# LightBox_Schematic_Updated_11-26.net
KiCad netlist of a schematic drawn in EAGLE
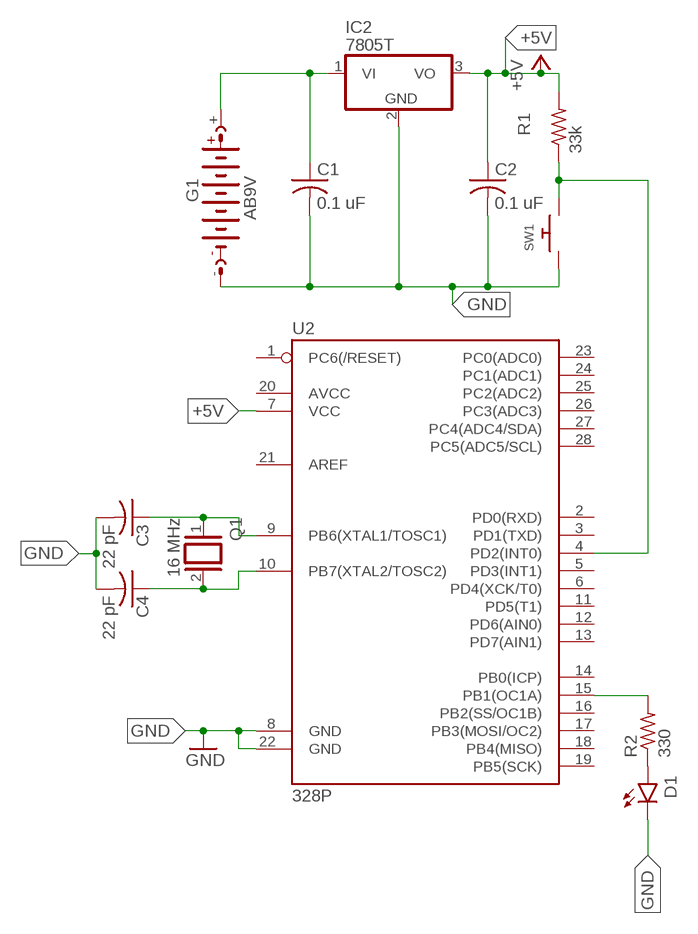
[diagram p0: schematic, sheet 1]

(export (version "E")
  (design (tool "Eeschema 10.0.6"))
  (components
    (comp (ref "C1")
      (value "0.1 uF")
      (footprint "eagle-import:C0805")
      (libsource (lib "eagle-import") (part "C-USC0805"))
    )
    (comp (ref "C2")
      (value "0.1 uF")
      (footprint "eagle-import:C0805")
      (libsource (lib "eagle-import") (part "C-USC0805"))
    )
    (comp (ref "C3")
      (value "22 pF")
      (footprint "eagle-import:C0805")
      (libsource (lib "eagle-import") (part "C-USC0805"))
    )
    (comp (ref "C4")
      (value "22 pF")
      (footprint "eagle-import:C0805")
      (libsource (lib "eagle-import") (part "C-USC0805"))
    )
    (comp (ref "D1")
      (value "LED3MM")
      (footprint "eagle-import:LED_3MM")
      (libsource (lib "eagle-import") (part "LED3MM"))
    )
    (comp (ref "G1")
      (value "AB9V")
      (footprint "eagle-import:AB9V")
      (libsource (lib "eagle-import") (part "AB9V"))
    )
    (comp (ref "IC2")
      (value "7805T")
      (footprint "eagle-import:TO220H")
      (libsource (lib "eagle-import") (part "78T05"))
    )
    (comp (ref "Q1")
      (value "16 MHz")
      (footprint "eagle-import:QS")
      (libsource (lib "eagle-import") (part "XTAL/S"))
    )
    (comp (ref "R1")
      (value "33k")
      (footprint "eagle-import:R0805")
      (libsource (lib "eagle-import") (part "R-US_R0805"))
    )
    (comp (ref "R2")
      (value "330")
      (footprint "eagle-import:R0805")
      (libsource (lib "eagle-import") (part "R-US_R0805"))
    )
    (comp (ref "SW1")
      (value "SWITCH_PUSHBUTTONEVQ-PE")
      (footprint "eagle-import:TACT_PANA-EVQ")
      (libsource (lib "eagle-import") (part "SWITCH_PUSHBUTTONEVQ-PE"))
    )
    (comp (ref "U2")
      (value "328P")
      (footprint "eagle-import:DIP28")
      (libsource (lib "eagle-import") (part "ATMEGA328P_PDIP"))
    )
  )
  (nets
    (net (code "1") (name "+5V") (class "Default")
      (node (ref "C2") (pin "1") (pinfunction "1_1") (pintype "passive"))
      (node (ref "IC2") (pin "3") (pinfunction "VO_3") (pintype "passive"))
      (node (ref "R1") (pin "1") (pinfunction "1_1") (pintype "passive"))
      (node (ref "R1") (pin "2") (pinfunction "2_2") (pintype "passive"))
      (node (ref "SW1") (pin "P$2") (pinfunction "P$2_P$2") (pintype "passive"))
      (node (ref "U2") (pin "4") (pinfunction "PD2(INT0)_4") (pintype "bidirectional"))
      (node (ref "U2") (pin "7") (pinfunction "VCC_7") (pintype "bidirectional"))
    )
    (net (code "2") (name "GND") (class "Default")
      (node (ref "C1") (pin "2") (pinfunction "2_2") (pintype "passive"))
      (node (ref "C2") (pin "2") (pinfunction "2_2") (pintype "passive"))
      (node (ref "C3") (pin "2") (pinfunction "2_2") (pintype "passive"))
      (node (ref "C4") (pin "2") (pinfunction "2_2") (pintype "passive"))
      (node (ref "D1") (pin "K") (pinfunction "C_K") (pintype "passive"))
      (node (ref "G1") (pin "-") (pinfunction "-_-") (pintype "passive"))
      (node (ref "IC2") (pin "2") (pinfunction "GND_2") (pintype "passive"))
      (node (ref "SW1") (pin "P$1") (pinfunction "P$1_P$1") (pintype "passive"))
      (node (ref "U2") (pin "22") (pinfunction "GND_22") (pintype "bidirectional"))
      (node (ref "U2") (pin "8") (pinfunction "GND_8") (pintype "bidirectional"))
    )
    (net (code "3") (name "Net-(D1-PadA)") (class "Default")
      (node (ref "D1") (pin "A") (pinfunction "A_A") (pintype "passive"))
      (node (ref "R2") (pin "1") (pinfunction "1_1") (pintype "passive"))
    )
    (net (code "4") (name "Net-(IC2-VI)") (class "Default")
      (node (ref "C1") (pin "1") (pinfunction "1_1") (pintype "passive"))
      (node (ref "G1") (pin "+") (pinfunction "+_+") (pintype "passive"))
      (node (ref "IC2") (pin "1") (pinfunction "VI_1") (pintype "input"))
    )
    (net (code "5") (name "Net-(U2-PB1(OC1A))") (class "Default")
      (node (ref "R2") (pin "2") (pinfunction "2_2") (pintype "passive"))
      (node (ref "U2") (pin "15") (pinfunction "PB1(OC1A)_15") (pintype "bidirectional"))
    )
    (net (code "6") (name "Net-(U2-PB6(XTAL1{slash}TOSC1))") (class "Default")
      (node (ref "C3") (pin "1") (pinfunction "1_1") (pintype "passive"))
      (node (ref "Q1") (pin "1") (pinfunction "1_1") (pintype "passive"))
      (node (ref "U2") (pin "9") (pinfunction "PB6(XTAL1/TOSC1)_9") (pintype "bidirectional"))
    )
    (net (code "7") (name "Net-(U2-PB7(XTAL2{slash}TOSC2))") (class "Default")
      (node (ref "C4") (pin "1") (pinfunction "1_1") (pintype "passive"))
      (node (ref "Q1") (pin "2") (pinfunction "2_2") (pintype "passive"))
      (node (ref "U2") (pin "10") (pinfunction "PB7(XTAL2/TOSC2)_10") (pintype "bidirectional"))
    )
    (net (code "8") (name "unconnected-(U2-AREF-Pad21)") (class "Default")
      (node (ref "U2") (pin "21") (pinfunction "AREF_21") (pintype "bidirectional"))
    )
    (net (code "9") (name "unconnected-(U2-AVCC-Pad20)") (class "Default")
      (node (ref "U2") (pin "20") (pinfunction "AVCC_20") (pintype "bidirectional"))
    )
    (net (code "10") (name "unconnected-(U2-PB0(ICP)-Pad14)") (class "Default")
      (node (ref "U2") (pin "14") (pinfunction "PB0(ICP)_14") (pintype "bidirectional"))
    )
    (net (code "11") (name "unconnected-(U2-PB2(SS{slash}OC1B)-Pad16)") (class "Default")
      (node (ref "U2") (pin "16") (pinfunction "PB2(SS/OC1B)_16") (pintype "bidirectional"))
    )
    (net (code "12") (name "unconnected-(U2-PB3(MOSI{slash}OC2)-Pad17)") (class "Default")
      (node (ref "U2") (pin "17") (pinfunction "PB3(MOSI/OC2)_17") (pintype "bidirectional"))
    )
    (net (code "13") (name "unconnected-(U2-PB4(MISO)-Pad18)") (class "Default")
      (node (ref "U2") (pin "18") (pinfunction "PB4(MISO)_18") (pintype "bidirectional"))
    )
    (net (code "14") (name "unconnected-(U2-PB5(SCK)-Pad19)") (class "Default")
      (node (ref "U2") (pin "19") (pinfunction "PB5(SCK)_19") (pintype "bidirectional"))
    )
    (net (code "15") (name "unconnected-(U2-PC0(ADC0)-Pad23)") (class "Default")
      (node (ref "U2") (pin "23") (pinfunction "PC0(ADC0)_23") (pintype "bidirectional"))
    )
    (net (code "16") (name "unconnected-(U2-PC1(ADC1)-Pad24)") (class "Default")
      (node (ref "U2") (pin "24") (pinfunction "PC1(ADC1)_24") (pintype "bidirectional"))
    )
    (net (code "17") (name "unconnected-(U2-PC2(ADC2)-Pad25)") (class "Default")
      (node (ref "U2") (pin "25") (pinfunction "PC2(ADC2)_25") (pintype "bidirectional"))
    )
    (net (code "18") (name "unconnected-(U2-PC3(ADC3)-Pad26)") (class "Default")
      (node (ref "U2") (pin "26") (pinfunction "PC3(ADC3)_26") (pintype "bidirectional"))
    )
    (net (code "19") (name "unconnected-(U2-PC4(ADC4{slash}SDA)-Pad27)") (class "Default")
      (node (ref "U2") (pin "27") (pinfunction "PC4(ADC4/SDA)_27") (pintype "bidirectional"))
    )
    (net (code "20") (name "unconnected-(U2-PC5(ADC5{slash}SCL)-Pad28)") (class "Default")
      (node (ref "U2") (pin "28") (pinfunction "PC5(ADC5/SCL)_28") (pintype "bidirectional"))
    )
    (net (code "21") (name "unconnected-(U2-PC6({slash}RESET)-Pad1)") (class "Default")
      (node (ref "U2") (pin "1") (pinfunction "PC6(/RESET)_1") (pintype "bidirectional"))
    )
    (net (code "22") (name "unconnected-(U2-PD0(RXD)-Pad2)") (class "Default")
      (node (ref "U2") (pin "2") (pinfunction "PD0(RXD)_2") (pintype "bidirectional"))
    )
    (net (code "23") (name "unconnected-(U2-PD1(TXD)-Pad3)") (class "Default")
      (node (ref "U2") (pin "3") (pinfunction "PD1(TXD)_3") (pintype "bidirectional"))
    )
    (net (code "24") (name "unconnected-(U2-PD3(INT1)-Pad5)") (class "Default")
      (node (ref "U2") (pin "5") (pinfunction "PD3(INT1)_5") (pintype "bidirectional"))
    )
    (net (code "25") (name "unconnected-(U2-PD4(XCK{slash}T0)-Pad6)") (class "Default")
      (node (ref "U2") (pin "6") (pinfunction "PD4(XCK/T0)_6") (pintype "bidirectional"))
    )
    (net (code "26") (name "unconnected-(U2-PD5(T1)-Pad11)") (class "Default")
      (node (ref "U2") (pin "11") (pinfunction "PD5(T1)_11") (pintype "bidirectional"))
    )
    (net (code "27") (name "unconnected-(U2-PD6(AIN0)-Pad12)") (class "Default")
      (node (ref "U2") (pin "12") (pinfunction "PD6(AIN0)_12") (pintype "bidirectional"))
    )
    (net (code "28") (name "unconnected-(U2-PD7(AIN1)-Pad13)") (class "Default")
      (node (ref "U2") (pin "13") (pinfunction "PD7(AIN1)_13") (pintype "bidirectional"))
    )
  )
)
